# FlasherHighpower.net
KiCad netlist of a schematic drawn in EAGLE
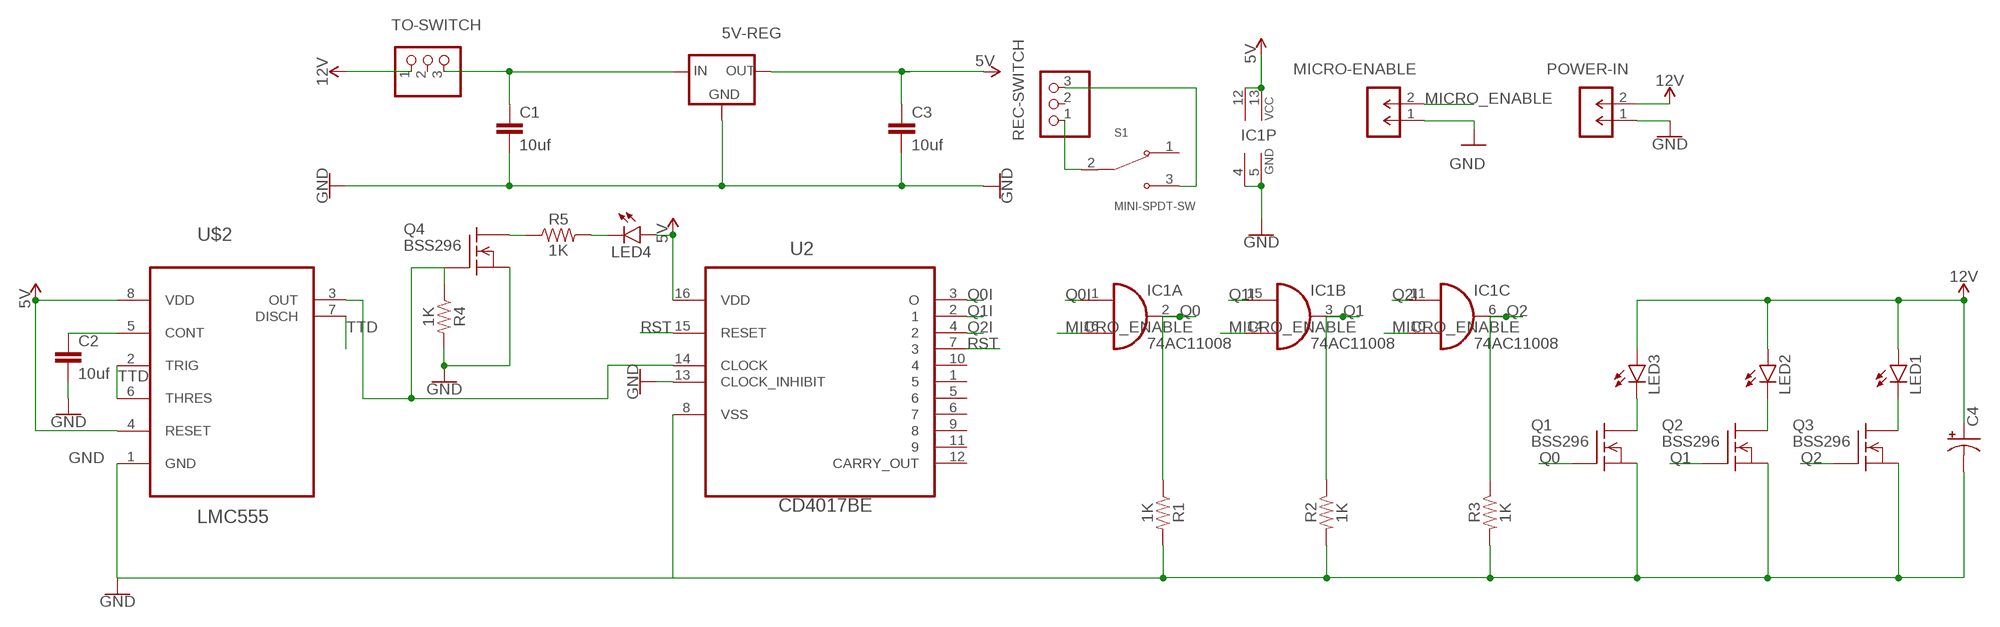
[diagram p0: schematic, sheet 1]

(export (version "E")
  (design (tool "Eeschema 10.0.6"))
  (components
    (comp (ref "5V-REG")
      (value "LD1117V33")
      (footprint "eagle-import:LD1117V33")
      (libsource (lib "eagle-import") (part "LD1117V33"))
    )
    (comp (ref "C1")
      (value "10uf")
      (footprint "eagle-import:C2.5-3")
      (libsource (lib "eagle-import") (part "C2,5-3"))
    )
    (comp (ref "C2")
      (value "10uf")
      (footprint "eagle-import:C2.5-3")
      (libsource (lib "eagle-import") (part "C2,5-3"))
    )
    (comp (ref "C3")
      (value "10uf")
      (footprint "eagle-import:C2.5-3")
      (libsource (lib "eagle-import") (part "C2,5-3"))
    )
    (comp (ref "C4")
      (value "CPOL-USE3.5-8")
      (footprint "eagle-import:E3,5-8")
      (libsource (lib "eagle-import") (part "CPOL-USE3.5-8"))
    )
    (comp (ref "IC1")
      (value "74AC11008")
      (footprint "eagle-import:DIL16")
      (libsource (lib "eagle-import") (part "74AC11008"))
    )
    (comp (ref "LED1")
      (value "LED5MM")
      (footprint "eagle-import:LED5MM")
      (fields (field (name "SPICEPREFIX") "L"))
      (libsource (lib "eagle-import") (part "LED5MM"))
    )
    (comp (ref "LED2")
      (value "LED5MM")
      (footprint "eagle-import:LED5MM")
      (fields (field (name "SPICEPREFIX") "L"))
      (libsource (lib "eagle-import") (part "LED5MM"))
    )
    (comp (ref "LED3")
      (value "LED5MM")
      (footprint "eagle-import:LED5MM")
      (fields (field (name "SPICEPREFIX") "L"))
      (libsource (lib "eagle-import") (part "LED5MM"))
    )
    (comp (ref "LED4")
      (value "LED5MM")
      (footprint "eagle-import:LED5MM")
      (fields (field (name "SPICEPREFIX") "L"))
      (libsource (lib "eagle-import") (part "LED5MM"))
    )
    (comp (ref "MICRO-ENABLE")
      (value "M-1X02-SIP-100-40Y")
      (footprint "eagle-import:SIP-100-02-40Y")
      (libsource (lib "eagle-import") (part "M-1X02-SIP-100-40Y"))
    )
    (comp (ref "POWER-IN")
      (value "M-1X02-SIP-100-40Y")
      (footprint "eagle-import:SIP-100-02-40Y")
      (libsource (lib "eagle-import") (part "M-1X02-SIP-100-40Y"))
    )
    (comp (ref "Q1")
      (value "BSS296")
      (footprint "eagle-import:TO92")
      (libsource (lib "eagle-import") (part "BSS296"))
    )
    (comp (ref "Q2")
      (value "BSS296")
      (footprint "eagle-import:TO92")
      (libsource (lib "eagle-import") (part "BSS296"))
    )
    (comp (ref "Q3")
      (value "BSS296")
      (footprint "eagle-import:TO92")
      (libsource (lib "eagle-import") (part "BSS296"))
    )
    (comp (ref "Q4")
      (value "BSS296")
      (footprint "eagle-import:TO92")
      (libsource (lib "eagle-import") (part "BSS296"))
    )
    (comp (ref "R1")
      (value "1K")
      (footprint "eagle-import:AXIAL-0.3")
      (libsource (lib "eagle-import") (part "10MOHM-HORIZ-1/4W-5%"))
    )
    (comp (ref "R2")
      (value "1K")
      (footprint "eagle-import:AXIAL-0.3")
      (libsource (lib "eagle-import") (part "10MOHM-HORIZ-1/4W-5%"))
    )
    (comp (ref "R3")
      (value "1K")
      (footprint "eagle-import:AXIAL-0.3")
      (libsource (lib "eagle-import") (part "10MOHM-HORIZ-1/4W-5%"))
    )
    (comp (ref "R4")
      (value "1K")
      (footprint "eagle-import:AXIAL-0.3")
      (libsource (lib "eagle-import") (part "10MOHM-HORIZ-1/4W-5%"))
    )
    (comp (ref "R5")
      (value "1K")
      (footprint "eagle-import:AXIAL-0.3")
      (libsource (lib "eagle-import") (part "10MOHM-HORIZ-1/4W-5%"))
    )
    (comp (ref "REC-SWITCH")
      (value "PINHD-1X3CB")
      (footprint "eagle-import:1X03-CLEANBIG")
      (libsource (lib "eagle-import") (part "PINHD-1X3CB"))
    )
    (comp (ref "S1")
      (value "MINI-SPDT-SW")
      (footprint "eagle-import:SW_MINI-SPDT-SW")
      (fields (field (name "MF") "Gravitech"))
      (libsource (lib "eagle-import") (part "MINI-SPDT-SW"))
    )
    (comp (ref "TO-SWITCH")
      (value "PINHD-1X3CB")
      (footprint "eagle-import:1X03-CLEANBIG")
      (libsource (lib "eagle-import") (part "PINHD-1X3CB"))
    )
    (comp (ref "U$2")
      (value "LMC555")
      (footprint "eagle-import:8-DIP")
      (fields (field (name "MF") "Texas Instruments") (field (name "MP") "LMC-555"))
      (libsource (lib "eagle-import") (part "LMC555"))
    )
    (comp (ref "U2")
      (value "CD4017BE")
      (footprint "eagle-import:DIP254P762X508-16")
      (fields (field (name "MF") "Texas"))
      (libsource (lib "eagle-import") (part "CD4017BE"))
    )
  )
  (nets
    (net (code "1") (name "/MICRO_ENABLE") (class "Default")
      (node (ref "IC1") (pin "10") (pinfunction "I1_10") (pintype "input"))
      (node (ref "IC1") (pin "14") (pinfunction "I1_14") (pintype "input"))
      (node (ref "IC1") (pin "16") (pinfunction "I1_16") (pintype "input"))
      (node (ref "MICRO-ENABLE") (pin "2") (pinfunction "2_2") (pintype "passive"))
    )
    (net (code "2") (name "/Q0") (class "Default")
      (node (ref "IC1") (pin "2") (pinfunction "O_2") (pintype "output"))
      (node (ref "Q1") (pin "1") (pinfunction "G_1") (pintype "passive"))
      (node (ref "R1") (pin "P$1") (pinfunction "1_P$1") (pintype "passive"))
    )
    (net (code "3") (name "/Q0I") (class "Default")
      (node (ref "IC1") (pin "1") (pinfunction "I0_1") (pintype "input"))
      (node (ref "U2") (pin "3") (pinfunction "O_3") (pintype "output"))
    )
    (net (code "4") (name "/Q1") (class "Default")
      (node (ref "IC1") (pin "3") (pinfunction "O_3") (pintype "output"))
      (node (ref "Q2") (pin "1") (pinfunction "G_1") (pintype "passive"))
      (node (ref "R2") (pin "P$1") (pinfunction "1_P$1") (pintype "passive"))
    )
    (net (code "5") (name "/Q1I") (class "Default")
      (node (ref "IC1") (pin "15") (pinfunction "I0_15") (pintype "input"))
      (node (ref "U2") (pin "2") (pinfunction "1_2") (pintype "output"))
    )
    (net (code "6") (name "/Q2") (class "Default")
      (node (ref "IC1") (pin "6") (pinfunction "O_6") (pintype "output"))
      (node (ref "Q3") (pin "1") (pinfunction "G_1") (pintype "passive"))
      (node (ref "R3") (pin "P$1") (pinfunction "1_P$1") (pintype "passive"))
    )
    (net (code "7") (name "/Q2I") (class "Default")
      (node (ref "IC1") (pin "11") (pinfunction "I0_11") (pintype "input"))
      (node (ref "U2") (pin "4") (pinfunction "2_4") (pintype "output"))
    )
    (net (code "8") (name "/RST") (class "Default")
      (node (ref "U2") (pin "15") (pinfunction "RESET_15") (pintype "input"))
      (node (ref "U2") (pin "7") (pinfunction "3_7") (pintype "output"))
    )
    (net (code "9") (name "/TTD") (class "Default")
      (node (ref "U$2") (pin "2") (pinfunction "TRIG_2") (pintype "input"))
      (node (ref "U$2") (pin "6") (pinfunction "THRES_6") (pintype "input"))
      (node (ref "U$2") (pin "7") (pinfunction "DISCH_7") (pintype "output"))
    )
    (net (code "10") (name "5V") (class "Default")
      (node (ref "5V-REG") (pin "OUT") (pinfunction "OUT_OUT") (pintype "output"))
      (node (ref "C3") (pin "1") (pinfunction "1_1") (pintype "passive"))
      (node (ref "IC1") (pin "12") (pinfunction "VCC_12") (pintype "power_in"))
      (node (ref "IC1") (pin "13") (pinfunction "VCC_13") (pintype "power_in"))
      (node (ref "LED4") (pin "A") (pinfunction "A_A") (pintype "passive"))
      (node (ref "U$2") (pin "4") (pinfunction "RESET_4") (pintype "input"))
      (node (ref "U$2") (pin "8") (pinfunction "VDD_8") (pintype "power_in"))
      (node (ref "U2") (pin "16") (pinfunction "VDD_16") (pintype "power_in"))
    )
    (net (code "11") (name "12V") (class "Default")
      (node (ref "C4") (pin "+") (pinfunction "+_+") (pintype "passive"))
      (node (ref "LED1") (pin "A") (pinfunction "A_A") (pintype "passive"))
      (node (ref "LED2") (pin "A") (pinfunction "A_A") (pintype "passive"))
      (node (ref "LED3") (pin "A") (pinfunction "A_A") (pintype "passive"))
      (node (ref "POWER-IN") (pin "2") (pinfunction "2_2") (pintype "passive"))
      (node (ref "TO-SWITCH") (pin "1") (pinfunction "1_1") (pintype "passive"))
    )
    (net (code "12") (name "GND") (class "Default")
      (node (ref "5V-REG") (pin "GND") (pinfunction "GND_GND") (pintype "input"))
      (node (ref "C1") (pin "2") (pinfunction "2_2") (pintype "passive"))
      (node (ref "C2") (pin "2") (pinfunction "2_2") (pintype "passive"))
      (node (ref "C3") (pin "2") (pinfunction "2_2") (pintype "passive"))
      (node (ref "C4") (pin "-") (pinfunction "-_-") (pintype "passive"))
      (node (ref "IC1") (pin "4") (pinfunction "GND_4") (pintype "power_in"))
      (node (ref "IC1") (pin "5") (pinfunction "GND_5") (pintype "power_in"))
      (node (ref "MICRO-ENABLE") (pin "1") (pinfunction "1_1") (pintype "passive"))
      (node (ref "POWER-IN") (pin "1") (pinfunction "1_1") (pintype "passive"))
      (node (ref "Q1") (pin "3") (pinfunction "S_3") (pintype "passive"))
      (node (ref "Q2") (pin "3") (pinfunction "S_3") (pintype "passive"))
      (node (ref "Q3") (pin "3") (pinfunction "S_3") (pintype "passive"))
      (node (ref "Q4") (pin "3") (pinfunction "S_3") (pintype "passive"))
      (node (ref "R1") (pin "P$2") (pinfunction "2_P$2") (pintype "passive"))
      (node (ref "R2") (pin "P$2") (pinfunction "2_P$2") (pintype "passive"))
      (node (ref "R3") (pin "P$2") (pinfunction "2_P$2") (pintype "passive"))
      (node (ref "R4") (pin "P$2") (pinfunction "2_P$2") (pintype "passive"))
      (node (ref "U$2") (pin "1") (pinfunction "GND_1") (pintype "passive"))
      (node (ref "U2") (pin "13") (pinfunction "CLOCK_INHIBIT_13") (pintype "input"))
      (node (ref "U2") (pin "8") (pinfunction "VSS_8") (pintype "power_in"))
    )
    (net (code "13") (name "Net-(5V-REG-PadIN)") (class "Default")
      (node (ref "5V-REG") (pin "IN") (pinfunction "IN_IN") (pintype "input"))
      (node (ref "C1") (pin "1") (pinfunction "1_1") (pintype "passive"))
      (node (ref "TO-SWITCH") (pin "3") (pinfunction "3_3") (pintype "passive"))
    )
    (net (code "14") (name "Net-(LED1-C)") (class "Default")
      (node (ref "LED1") (pin "K") (pinfunction "C_K") (pintype "passive"))
      (node (ref "Q3") (pin "2") (pinfunction "D_2") (pintype "passive"))
    )
    (net (code "15") (name "Net-(LED2-C)") (class "Default")
      (node (ref "LED2") (pin "K") (pinfunction "C_K") (pintype "passive"))
      (node (ref "Q2") (pin "2") (pinfunction "D_2") (pintype "passive"))
    )
    (net (code "16") (name "Net-(LED3-C)") (class "Default")
      (node (ref "LED3") (pin "K") (pinfunction "C_K") (pintype "passive"))
      (node (ref "Q1") (pin "2") (pinfunction "D_2") (pintype "passive"))
    )
    (net (code "17") (name "Net-(LED4-C)") (class "Default")
      (node (ref "LED4") (pin "K") (pinfunction "C_K") (pintype "passive"))
      (node (ref "R5") (pin "P$2") (pinfunction "2_P$2") (pintype "passive"))
    )
    (net (code "18") (name "Net-(Q4-D)") (class "Default")
      (node (ref "Q4") (pin "2") (pinfunction "D_2") (pintype "passive"))
      (node (ref "R5") (pin "P$1") (pinfunction "1_P$1") (pintype "passive"))
    )
    (net (code "19") (name "Net-(Q4-G)") (class "Default")
      (node (ref "Q4") (pin "1") (pinfunction "G_1") (pintype "passive"))
      (node (ref "R4") (pin "P$1") (pinfunction "1_P$1") (pintype "passive"))
      (node (ref "U$2") (pin "3") (pinfunction "OUT_3") (pintype "output"))
      (node (ref "U2") (pin "14") (pinfunction "CLOCK_14") (pintype "input"))
    )
    (net (code "20") (name "Net-(REC-SWITCH-Pad1)") (class "Default")
      (node (ref "REC-SWITCH") (pin "1") (pinfunction "1_1") (pintype "passive"))
      (node (ref "S1") (pin "2") (pinfunction "2_2") (pintype "passive"))
    )
    (net (code "21") (name "Net-(REC-SWITCH-Pad3)") (class "Default")
      (node (ref "REC-SWITCH") (pin "3") (pinfunction "3_3") (pintype "passive"))
      (node (ref "S1") (pin "3") (pinfunction "3_3") (pintype "passive"))
    )
    (net (code "22") (name "Net-(U$2-CONT)") (class "Default")
      (node (ref "C2") (pin "1") (pinfunction "1_1") (pintype "passive"))
      (node (ref "U$2") (pin "5") (pinfunction "CONT_5") (pintype "input"))
    )
    (net (code "23") (name "unconnected-(REC-SWITCH-Pad2)") (class "Default")
      (node (ref "REC-SWITCH") (pin "2") (pinfunction "2_2") (pintype "passive"))
    )
    (net (code "24") (name "unconnected-(S1-Pad1)") (class "Default")
      (node (ref "S1") (pin "1") (pinfunction "1_1") (pintype "passive"))
    )
    (net (code "25") (name "unconnected-(TO-SWITCH-Pad2)") (class "Default")
      (node (ref "TO-SWITCH") (pin "2") (pinfunction "2_2") (pintype "passive"))
    )
    (net (code "26") (name "unconnected-(U2-4-Pad10)") (class "Default")
      (node (ref "U2") (pin "10") (pinfunction "4_10") (pintype "output"))
    )
    (net (code "27") (name "unconnected-(U2-5-Pad1)") (class "Default")
      (node (ref "U2") (pin "1") (pinfunction "5_1") (pintype "output"))
    )
    (net (code "28") (name "unconnected-(U2-6-Pad5)") (class "Default")
      (node (ref "U2") (pin "5") (pinfunction "6_5") (pintype "output"))
    )
    (net (code "29") (name "unconnected-(U2-7-Pad6)") (class "Default")
      (node (ref "U2") (pin "6") (pinfunction "7_6") (pintype "output"))
    )
    (net (code "30") (name "unconnected-(U2-8-Pad9)") (class "Default")
      (node (ref "U2") (pin "9") (pinfunction "8_9") (pintype "output"))
    )
    (net (code "31") (name "unconnected-(U2-9-Pad11)") (class "Default")
      (node (ref "U2") (pin "11") (pinfunction "9_11") (pintype "output"))
    )
    (net (code "32") (name "unconnected-(U2-CARRY_OUT-Pad12)") (class "Default")
      (node (ref "U2") (pin "12") (pinfunction "CARRY_OUT_12") (pintype "output"))
    )
  )
)
